# flyBuck_test.net
KiCad netlist of a schematic drawn in EasyEDA Pro
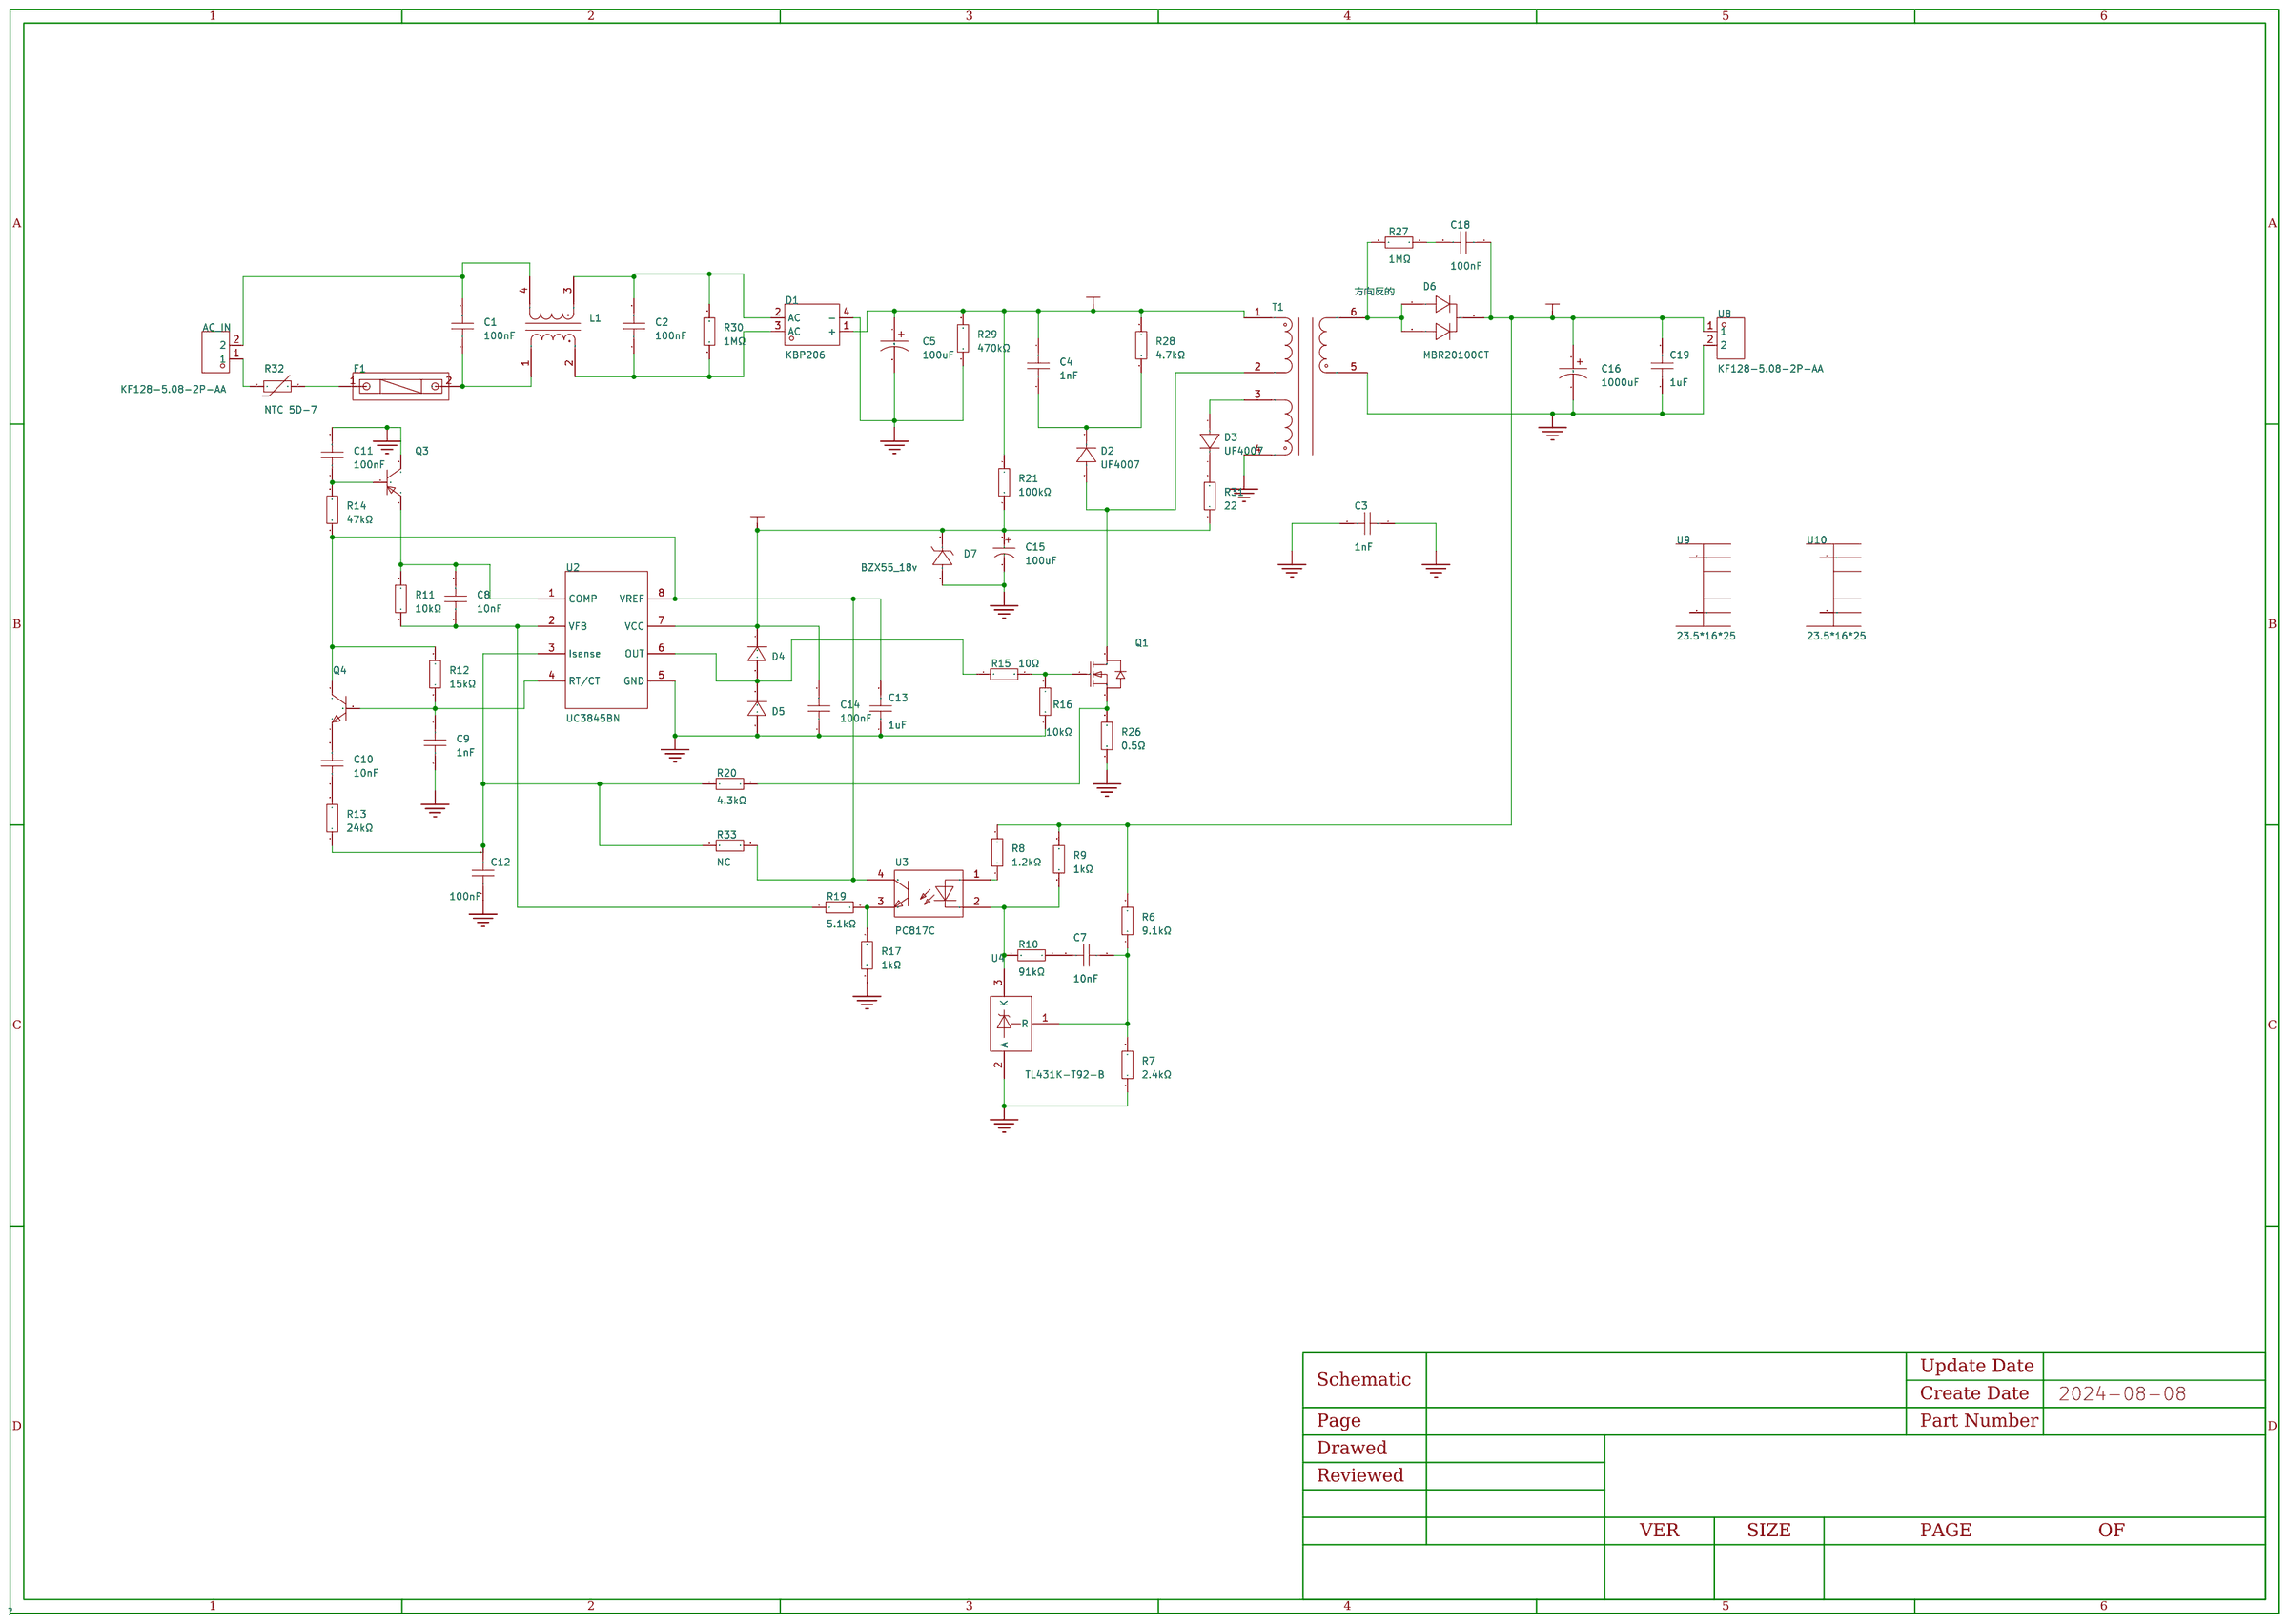
[diagram p0: schematic sheet]

(export (version "E")
  (design (tool "Eeschema 10.0.6"))
  (components
    (comp (ref "AC_IN")
      (value "KF128-5.08-2P-AA")
      (footprint "easyedapro:CONN-TH_P5.08_KF128-5.08-2P")
      (fields (field (name "Manufacturer") "KEFA(科发)"))
      (libsource (lib "easyedapro") (part "KF128-5.08-2P"))
    )
    (comp (ref "C1")
      (value "100nF")
      (footprint "easyedapro:CAP-TH_L13.0-W6.0-P10.0-D0.6")
      (description "容值:100nF;精度:±10%;电压(AC):275V;等级:X2;")
      (fields (field (name "Manufacturer Part") "X2-104K-275VAC") (field (name "Manufacturer") "NDF(达孚)"))
      (libsource (lib "easyedapro") (part "X2-104K-275VAC_C914483"))
    )
    (comp (ref "C2")
      (value "100nF")
      (footprint "easyedapro:CAP-TH_L13.0-W6.0-P10.0-D0.6")
      (description "容值:100nF;精度:±10%;电压(AC):275V;等级:X2;")
      (fields (field (name "Manufacturer Part") "X2-104K-275VAC") (field (name "Manufacturer") "NDF(达孚)"))
      (libsource (lib "easyedapro") (part "X2-104K-275VAC_C914483"))
    )
    (comp (ref "C3")
      (value "1nF")
      (footprint "easyedapro:CAP-TH_L7.0-W3.5-P10.00-D0.6")
      (description "容值:68pF;精度:±10%;电压(AC):400V;等级:Y1;")
      (fields
        (field (name "Manufacturer Part") "Y1680K-E1I-B4-AC400V")
        (field (name "Manufacturer") "Dersonic(德尔创)")
      )
      (libsource (lib "easyedapro") (part "Y1680K-E1I-B4-AC400V"))
    )
    (comp (ref "C4")
      (value "1nF")
      (footprint "easyedapro:CAP-TH_L7.0-W3.5-P10.00-D0.6")
      (description "容值:68pF;精度:±10%;电压(AC):400V;等级:Y1;")
      (fields
        (field (name "Manufacturer Part") "Y1680K-E1I-B4-AC400V")
        (field (name "Manufacturer") "Dersonic(德尔创)")
      )
      (libsource (lib "easyedapro") (part "Y1680K-E1I-B4-AC400V"))
    )
    (comp (ref "C5")
      (value "100uF")
      (footprint "easyedapro:CAP-TH_BD22.0-P10.00-D2.2-FD")
      (description "容值:100uF;精度:±20%;额定电压:400V;脚间距:10mm;纹波电流:630mA@120Hz;")
      (fields (field (name "Manufacturer Part") "152EC0349") (field (name "Manufacturer") "KNSCHA(科尼盛)"))
      (libsource (lib "easyedapro") (part "152EC0349"))
    )
    (comp (ref "C7")
      (value "10nF")
      (footprint "easyedapro:CAP-TH_L5.8-W2.4-P2.54-D0.6")
      (description "容值:100nF;精度:-20%~+80%;额定电压:50V;温度系数:Y5V;")
      (fields
        (field (name "Manufacturer Part") "CC1H104ZA1ED3F5P1100")
        (field (name "Manufacturer") "Dersonic(德尔创)")
      )
      (libsource (lib "easyedapro") (part "CC1H104ZA1ED3F5P1100"))
    )
    (comp (ref "C8")
      (value "10nF")
      (footprint "easyedapro:CAP-TH_L5.8-W2.4-P2.54-D0.6")
      (description "容值:100nF;精度:-20%~+80%;额定电压:50V;温度系数:Y5V;")
      (fields
        (field (name "Manufacturer Part") "CC1H104ZA1ED3F5P1100")
        (field (name "Manufacturer") "Dersonic(德尔创)")
      )
      (libsource (lib "easyedapro") (part "CC1H104ZA1ED3F5P1100"))
    )
    (comp (ref "C9")
      (value "1nF")
      (footprint "easyedapro:CAP-TH_L5.8-W2.4-P2.54-D0.6")
      (description "容值:100nF;精度:-20%~+80%;额定电压:50V;温度系数:Y5V;")
      (fields
        (field (name "Manufacturer Part") "CC1H104ZA1ED3F5P1100")
        (field (name "Manufacturer") "Dersonic(德尔创)")
      )
      (libsource (lib "easyedapro") (part "CC1H104ZA1ED3F5P1100"))
    )
    (comp (ref "C10")
      (value "10nF")
      (footprint "easyedapro:CAP-TH_L5.8-W2.4-P2.54-D0.6")
      (description "容值:100nF;精度:-20%~+80%;额定电压:50V;温度系数:Y5V;")
      (fields
        (field (name "Manufacturer Part") "CC1H104ZA1ED3F5P1100")
        (field (name "Manufacturer") "Dersonic(德尔创)")
      )
      (libsource (lib "easyedapro") (part "CC1H104ZA1ED3F5P1100"))
    )
    (comp (ref "C11")
      (value "100nF")
      (footprint "easyedapro:CAP-TH_L5.8-W2.4-P2.54-D0.6")
      (description "容值:100nF;精度:-20%~+80%;额定电压:50V;温度系数:Y5V;")
      (fields
        (field (name "Manufacturer Part") "CC1H104ZA1ED3F5P1100")
        (field (name "Manufacturer") "Dersonic(德尔创)")
      )
      (libsource (lib "easyedapro") (part "CC1H104ZA1ED3F5P1100"))
    )
    (comp (ref "C12")
      (value "100nF")
      (footprint "easyedapro:CAP-TH_L5.8-W2.4-P2.54-D0.6")
      (description "容值:100nF;精度:-20%~+80%;额定电压:50V;温度系数:Y5V;")
      (fields
        (field (name "Manufacturer Part") "CC1H104ZA1ED3F5P1100")
        (field (name "Manufacturer") "Dersonic(德尔创)")
      )
      (libsource (lib "easyedapro") (part "CC1H104ZA1ED3F5P1100"))
    )
    (comp (ref "C13")
      (value "1uF")
      (footprint "easyedapro:CAP-TH_L6.0-W4.0-P5.00-D1.2")
      (description "等级：独石电容 104K50V  P5 容值：0.1uF 精度：±10% 额定电压：50V 独石电容  积层 X7R MLCC 多层陶瓷")
      (fields (field (name "Manufacturer Part") "CT40805B104K500F3") (field (name "Manufacturer") "KYET(科雅)"))
      (libsource (lib "easyedapro") (part "CT40805B104K500F3"))
    )
    (comp (ref "C14")
      (value "100nF")
      (footprint "easyedapro:CAP-TH_L5.8-W2.4-P2.54-D0.6")
      (description "容值:100nF;精度:-20%~+80%;额定电压:50V;温度系数:Y5V;")
      (fields
        (field (name "Manufacturer Part") "CC1H104ZA1ED3F5P1100")
        (field (name "Manufacturer") "Dersonic(德尔创)")
      )
      (libsource (lib "easyedapro") (part "CC1H104ZA1ED3F5P1100"))
    )
    (comp (ref "C15")
      (value "100uF")
      (footprint "easyedapro:CAP-TH_BD6.3-P2.50-D1.0-FD")
      (description "容值:100uF;精度:±20%;额定电压:25V;")
      (fields (field (name "Manufacturer Part") "ERS1EM101E11OT") (field (name "Manufacturer") "AISHI(艾华集团)"))
      (libsource (lib "easyedapro") (part "ERS1EM101E11OT"))
    )
    (comp (ref "C16")
      (value "1000uF")
      (footprint "easyedapro:CAP-TH_BD10.0-P5.00-D1.0-FD")
      (description "容值:1000uF;精度:±20%;额定电压:25V;纹波电流:450mA@120Hz;等效串联电阻:-;")
      (fields
        (field (name "Manufacturer Part") "01EC4294SHC1000UF25V")
        (field (name "Manufacturer") "KNSCHA(科尼盛)")
      )
      (libsource (lib "easyedapro") (part "01EC4294SHC1000UF25V"))
    )
    (comp (ref "C18")
      (value "100nF")
      (footprint "easyedapro:CAP-TH_L5.8-W2.4-P2.54-D0.6")
      (description "容值:100nF;精度:-20%~+80%;额定电压:50V;温度系数:Y5V;")
      (fields
        (field (name "Manufacturer Part") "CC1H104ZA1ED3F5P1100")
        (field (name "Manufacturer") "Dersonic(德尔创)")
      )
      (libsource (lib "easyedapro") (part "CC1H104ZA1ED3F5P1100"))
    )
    (comp (ref "C19")
      (value "1uF")
      (footprint "easyedapro:CAP-TH_L6.0-W4.0-P5.00-D1.2")
      (description "等级：独石电容 104K50V  P5 容值：0.1uF 精度：±10% 额定电压：50V 独石电容  积层 X7R MLCC 多层陶瓷")
      (fields (field (name "Manufacturer Part") "CT40805B104K500F3") (field (name "Manufacturer") "KYET(科雅)"))
      (libsource (lib "easyedapro") (part "CT40805B104K500F3"))
    )
    (comp (ref "D1")
      (value "KBP206")
      (footprint "easyedapro:KBP_4P-L14.5-W3.5-P3.81-L")
      (description "正向压降(Vf):1.1V@2A;直流反向耐压(Vr):600V;平均整流电流(Io):2A;正向浪涌电流(Ifsm):60A;")
      (fields (field (name "Manufacturer") "HXY MOSFET(华轩阳电子)"))
      (libsource (lib "easyedapro") (part "KBP206_C7507386"))
    )
    (comp (ref "D2")
      (value "UF4007")
      (footprint "easyedapro:DO-41_BD2.4-L4.7-P8.70-D0.9-RD")
      (description "二极管配置:-;正向压降(Vf):1.7V@1A;直流反向耐压(Vr):1kV;整流电流:1A;反向恢复时间(trr):75ns;")
      (fields (field (name "Manufacturer") "MDD(辰达半导体)"))
      (libsource (lib "easyedapro") (part "UF4007_C960666"))
    )
    (comp (ref "D3")
      (value "UF4007")
      (footprint "easyedapro:DO-41_BD2.4-L4.7-P8.70-D0.9-RD")
      (description "二极管配置:-;正向压降(Vf):1.7V@1A;直流反向耐压(Vr):1kV;整流电流:1A;反向恢复时间(trr):75ns;")
      (fields (field (name "Manufacturer") "MDD(辰达半导体)"))
      (libsource (lib "easyedapro") (part "UF4007_C960666"))
    )
    (comp (ref "D4")
      (value "1N4148")
      (footprint "easyedapro:DO-35_BD2.0-L4.2-P8.20-D0.5-RD")
      (description "二极管配置:-;正向压降(Vf):1V@10mA;直流反向耐压(Vr):75V;平均整流电流(Io):150mA;功率:500mW;反向恢复时间(trr):4ns;")
      (fields (field (name "Manufacturer") "LGE(鲁光)"))
      (libsource (lib "easyedapro") (part "1N4148_C402212"))
    )
    (comp (ref "D5")
      (value "1N4148")
      (footprint "easyedapro:DO-35_BD2.0-L4.2-P8.20-D0.5-RD")
      (description "二极管配置:-;正向压降(Vf):1V@10mA;直流反向耐压(Vr):75V;平均整流电流(Io):150mA;功率:500mW;反向恢复时间(trr):4ns;")
      (fields (field (name "Manufacturer") "LGE(鲁光)"))
      (libsource (lib "easyedapro") (part "1N4148_C402212"))
    )
    (comp (ref "D6")
      (value "MBR20100CT")
      (footprint "easyedapro:TO-220AB-3_L10.4-W4.6-P2.54-T")
      (description "二极管配置:1对共阴极;正向压降(Vf):850mV@10A;直流反向耐压(Vr):100V;整流电流:20A;")
      (fields (field (name "Manufacturer") "MDD(辰达半导体)"))
      (libsource (lib "easyedapro") (part "MBR20100CT_C173465"))
    )
    (comp (ref "D7")
      (value "BZX55_18v")
      (footprint "easyedapro:DO-35_BD1.7-L3.6-P10.00-D0.5-FD")
      (description "二极管配置:独立式;稳压值(标称值):9.1V;稳压值(范围):8.65V~9.56V;功率(Pd):500mW;")
      (fields (field (name "Manufacturer") "LGE(鲁光)"))
      (libsource (lib "easyedapro") (part "BZX55C9V1_C5158984"))
    )
    (comp (ref "F1")
      (value "5x20 BLX-A型 保险丝支架 XC-7")
      (footprint "easyedapro:FUSE-TH_L22.6-W9.0")
      (description "保险丝座类型:-;保险丝类型:-;")
      (fields (field (name "Manufacturer") "xcfuse(旭程)"))
      (libsource (lib "easyedapro") (part "5x20 BLX-Atype Fuse holder XC-7"))
    )
    (comp (ref "L1")
      (value "YDUU9.8-103L0301")
      (footprint "easyedapro:FILTER-TH_4P-L16.5-W11.5_YDUU9.8-603L0201")
      (description "线路数:2;电感 @ 频率:10mH@1KHz;")
      (fields (field (name "Manufacturer") "YJYCOIN(益嘉源)"))
      (libsource (lib "easyedapro") (part "YDUU9.8-103L0301"))
    )
    (comp (ref "Q1")
      (value "FQP6N80C")
      (footprint "easyedapro:TO-220-3_L10.2-W4.5-P2.54-L-1")
      (fields (field (name "Manufacturer") "onsemi(安森美)"))
      (libsource (lib "easyedapro") (part "FQP6N80C"))
    )
    (comp (ref "Q3")
      (value "S8550")
      (footprint "easyedapro:TO-92-3_L5.1-W4.1-P1.27-L")
      (description "晶体管类型:PNP;集电极电流(Ic):500mA;集射极击穿电压(Vceo):25V;功率(Pd):625mW;")
      (fields (field (name "Manufacturer") "Slkor(萨科微)"))
      (libsource (lib "easyedapro") (part "S8550_C2826361"))
    )
    (comp (ref "Q4")
      (value "S8050")
      (footprint "easyedapro:TO-92-3_L4.5-W3.5-P1.27-L")
      (description "晶体管类型:NPN;集电极电流(Ic):500mA;集射极击穿电压(Vceo):25V;功率(Pd):625mW;直流电流增益(hFE@Ic,Vce):160@50mA,1V;")
      (fields (field (name "Manufacturer") "JSMSEMI(杰盛微)"))
      (libsource (lib "easyedapro") (part "S8050_C2931492"))
    )
    (comp (ref "R6")
      (value "9.1kΩ")
      (footprint "easyedapro:RES-TH_BD1.9-L3.3-P7.30-D0.5")
      (description "电阻类型:金属膜电阻;阻值:1kΩ;精度:±1%;功率:125mW;温度系数:±50ppm/°C;")
      (fields
        (field (name "Manufacturer Part") "MFR0W8F1001A50")
        (field (name "Manufacturer") "UNI-ROYAL(厚声)")
      )
      (libsource (lib "easyedapro") (part "MFR0W8F1001A50"))
    )
    (comp (ref "R7")
      (value "2.4kΩ")
      (footprint "easyedapro:RES-TH_BD1.9-L3.3-P7.30-D0.5")
      (description "电阻类型:金属膜电阻;阻值:1kΩ;精度:±1%;功率:125mW;温度系数:±50ppm/°C;")
      (fields
        (field (name "Manufacturer Part") "MFR0W8F1001A50")
        (field (name "Manufacturer") "UNI-ROYAL(厚声)")
      )
      (libsource (lib "easyedapro") (part "MFR0W8F1001A50"))
    )
    (comp (ref "R8")
      (value "1.2kΩ")
      (footprint "easyedapro:RES-TH_BD1.9-L3.3-P7.30-D0.5")
      (description "电阻类型:金属膜电阻;阻值:1kΩ;精度:±1%;功率:125mW;温度系数:±50ppm/°C;")
      (fields
        (field (name "Manufacturer Part") "MFR0W8F1001A50")
        (field (name "Manufacturer") "UNI-ROYAL(厚声)")
      )
      (libsource (lib "easyedapro") (part "MFR0W8F1001A50"))
    )
    (comp (ref "R9")
      (value "1kΩ")
      (footprint "easyedapro:RES-TH_BD1.9-L3.3-P7.30-D0.5")
      (description "电阻类型:金属膜电阻;阻值:1kΩ;精度:±1%;功率:125mW;温度系数:±50ppm/°C;")
      (fields
        (field (name "Manufacturer Part") "MFR0W8F1001A50")
        (field (name "Manufacturer") "UNI-ROYAL(厚声)")
      )
      (libsource (lib "easyedapro") (part "MFR0W8F1001A50"))
    )
    (comp (ref "R10")
      (value "91kΩ")
      (footprint "easyedapro:RES-TH_BD1.9-L3.3-P7.30-D0.5")
      (description "电阻类型:金属膜电阻;阻值:1kΩ;精度:±1%;功率:125mW;温度系数:±50ppm/°C;")
      (fields
        (field (name "Manufacturer Part") "MFR0W8F1001A50")
        (field (name "Manufacturer") "UNI-ROYAL(厚声)")
      )
      (libsource (lib "easyedapro") (part "MFR0W8F1001A50"))
    )
    (comp (ref "R11")
      (value "10kΩ")
      (footprint "easyedapro:RES-TH_BD1.9-L3.3-P7.30-D0.5")
      (description "电阻类型:金属膜电阻;阻值:1kΩ;精度:±1%;功率:125mW;温度系数:±50ppm/°C;")
      (fields
        (field (name "Manufacturer Part") "MFR0W8F1001A50")
        (field (name "Manufacturer") "UNI-ROYAL(厚声)")
      )
      (libsource (lib "easyedapro") (part "MFR0W8F1001A50"))
    )
    (comp (ref "R12")
      (value "15kΩ")
      (footprint "easyedapro:RES-TH_BD1.9-L3.3-P7.30-D0.5")
      (description "电阻类型:金属膜电阻;阻值:1kΩ;精度:±1%;功率:125mW;温度系数:±50ppm/°C;")
      (fields
        (field (name "Manufacturer Part") "MFR0W8F1001A50")
        (field (name "Manufacturer") "UNI-ROYAL(厚声)")
      )
      (libsource (lib "easyedapro") (part "MFR0W8F1001A50"))
    )
    (comp (ref "R13")
      (value "24kΩ")
      (footprint "easyedapro:RES-TH_BD1.9-L3.3-P7.30-D0.5")
      (description "电阻类型:金属膜电阻;阻值:1kΩ;精度:±1%;功率:125mW;温度系数:±50ppm/°C;")
      (fields
        (field (name "Manufacturer Part") "MFR0W8F1001A50")
        (field (name "Manufacturer") "UNI-ROYAL(厚声)")
      )
      (libsource (lib "easyedapro") (part "MFR0W8F1001A50"))
    )
    (comp (ref "R14")
      (value "47kΩ")
      (footprint "easyedapro:RES-TH_BD1.9-L3.3-P7.30-D0.5")
      (description "电阻类型:金属膜电阻;阻值:1kΩ;精度:±1%;功率:125mW;温度系数:±50ppm/°C;")
      (fields
        (field (name "Manufacturer Part") "MFR0W8F1001A50")
        (field (name "Manufacturer") "UNI-ROYAL(厚声)")
      )
      (libsource (lib "easyedapro") (part "MFR0W8F1001A50"))
    )
    (comp (ref "R15")
      (value "10Ω")
      (footprint "easyedapro:RES-TH_BD1.9-L3.3-P7.30-D0.5")
      (description "电阻类型:金属膜电阻;阻值:1kΩ;精度:±1%;功率:125mW;温度系数:±50ppm/°C;")
      (fields
        (field (name "Manufacturer Part") "MFR0W8F1001A50")
        (field (name "Manufacturer") "UNI-ROYAL(厚声)")
      )
      (libsource (lib "easyedapro") (part "MFR0W8F1001A50"))
    )
    (comp (ref "R16")
      (value "10kΩ")
      (footprint "easyedapro:RES-TH_BD1.9-L3.3-P7.30-D0.5")
      (description "电阻类型:金属膜电阻;阻值:1kΩ;精度:±1%;功率:125mW;温度系数:±50ppm/°C;")
      (fields
        (field (name "Manufacturer Part") "MFR0W8F1001A50")
        (field (name "Manufacturer") "UNI-ROYAL(厚声)")
      )
      (libsource (lib "easyedapro") (part "MFR0W8F1001A50"))
    )
    (comp (ref "R17")
      (value "1kΩ")
      (footprint "easyedapro:RES-TH_BD1.9-L3.3-P7.30-D0.5")
      (description "电阻类型:金属膜电阻;阻值:1kΩ;精度:±1%;功率:125mW;温度系数:±50ppm/°C;")
      (fields
        (field (name "Manufacturer Part") "MFR0W8F1001A50")
        (field (name "Manufacturer") "UNI-ROYAL(厚声)")
      )
      (libsource (lib "easyedapro") (part "MFR0W8F1001A50"))
    )
    (comp (ref "R19")
      (value "5.1kΩ")
      (footprint "easyedapro:RES-TH_BD1.9-L3.3-P7.30-D0.5")
      (description "电阻类型:金属膜电阻;阻值:1kΩ;精度:±1%;功率:125mW;温度系数:±50ppm/°C;")
      (fields
        (field (name "Manufacturer Part") "MFR0W8F1001A50")
        (field (name "Manufacturer") "UNI-ROYAL(厚声)")
      )
      (libsource (lib "easyedapro") (part "MFR0W8F1001A50"))
    )
    (comp (ref "R20")
      (value "4.3kΩ")
      (footprint "easyedapro:RES-TH_BD1.9-L3.3-P7.30-D0.5")
      (description "电阻类型:金属膜电阻;阻值:1kΩ;精度:±1%;功率:125mW;温度系数:±50ppm/°C;")
      (fields
        (field (name "Manufacturer Part") "MFR0W8F1001A50")
        (field (name "Manufacturer") "UNI-ROYAL(厚声)")
      )
      (libsource (lib "easyedapro") (part "MFR0W8F1001A50"))
    )
    (comp (ref "R21")
      (value "100kΩ")
      (footprint "easyedapro:RES-TH_BD2.2-L6.5-P10.50-D0.6")
      (description "电阻类型:金属膜电阻;阻值:4.7kΩ;精度:±1%;功率:250mW;温度系数:±50ppm/°C;")
      (fields (field (name "Manufacturer Part") "MF1/4CCT52A4701F") (field (name "Manufacturer") "KOA"))
      (libsource (lib "easyedapro") (part "MF1/4CCT52A4701F"))
    )
    (comp (ref "R26")
      (value "0.5Ω")
      (footprint "easyedapro:R1206")
      (libsource (lib "easyedapro") (part "电阻"))
    )
    (comp (ref "R27")
      (value "1MΩ")
      (footprint "easyedapro:RES-TH_BD2.2-L6.5-P10.50-D0.6")
      (description "电阻类型:金属膜电阻;阻值:4.7kΩ;精度:±1%;功率:250mW;温度系数:±50ppm/°C;")
      (fields (field (name "Manufacturer Part") "MF1/4CCT52A4701F") (field (name "Manufacturer") "KOA"))
      (libsource (lib "easyedapro") (part "MF1/4CCT52A4701F"))
    )
    (comp (ref "R28")
      (value "4.7kΩ")
      (footprint "easyedapro:RES-TH_BD2.2-L6.5-P10.50-D0.6")
      (description "电阻类型:金属膜电阻;阻值:4.7kΩ;精度:±1%;功率:250mW;温度系数:±50ppm/°C;")
      (fields (field (name "Manufacturer Part") "MF1/4CCT52A4701F") (field (name "Manufacturer") "KOA"))
      (libsource (lib "easyedapro") (part "MF1/4CCT52A4701F"))
    )
    (comp (ref "R29")
      (value "470kΩ")
      (footprint "easyedapro:RES-TH_BD2.2-L6.5-P10.50-D0.6")
      (description "电阻类型:金属膜电阻;阻值:4.7kΩ;精度:±1%;功率:250mW;温度系数:±50ppm/°C;")
      (fields (field (name "Manufacturer Part") "MF1/4CCT52A4701F") (field (name "Manufacturer") "KOA"))
      (libsource (lib "easyedapro") (part "MF1/4CCT52A4701F"))
    )
    (comp (ref "R30")
      (value "1MΩ")
      (footprint "easyedapro:RES-TH_BD2.3-L6.5-P10.50-D0.5")
      (description "电阻类型:玻璃釉电阻;阻值:10kΩ;精度:±5%;功率:250mW;温度系数:±200ppm/°C;")
      (fields (field (name "Manufacturer Part") "RI40-1/4W-10KΩ±5%T") (field (name "Manufacturer") "华星机电"))
      (libsource (lib "easyedapro") (part "RI40-1/4W-10KΩ±5%T"))
    )
    (comp (ref "R31") (value "22") (footprint "easyedapro:R1206") (libsource (lib "easyedapro") (part "电阻")))
    (comp (ref "R32")
      (value "NTC 5D-7")
      (footprint "easyedapro:RES-TH_L8.5-W5.5-P5.00-D0.6-S5.50")
      (description "阻值(25°C):5Ω;B值(25°C/50°C):-;电阻精度:-;功率:-;B值精度:-;最大稳态电流(25°C):2A;")
      (fields (field (name "Manufacturer") "RUILON(瑞隆源)"))
      (libsource (lib "easyedapro") (part "NTC 5D-7"))
    )
    (comp (ref "R33")
      (value "NC")
      (footprint "easyedapro:RES-TH_BD1.9-L3.3-P7.30-D0.5")
      (description "电阻类型:金属膜电阻;阻值:1kΩ;精度:±1%;功率:125mW;温度系数:±50ppm/°C;")
      (fields
        (field (name "Manufacturer Part") "MFR0W8F1001A50")
        (field (name "Manufacturer") "UNI-ROYAL(厚声)")
      )
      (libsource (lib "easyedapro") (part "MFR0W8F1001A50"))
    )
    (comp (ref "T1")
      (value "~")
      (footprint "easyedapro:EE25_7P")
      (libsource (lib "easyedapro") (part "EE25_7P"))
    )
    (comp (ref "U2")
      (value "UC3845BN")
      (footprint "easyedapro:DIP-8_L10.9-W6.6-P2.54-LS7.6-BL")
      (description "电源电压:7.6V~30V;开关频率:500kHz;")
      (fields (field (name "Manufacturer") "ST(意法半导体)"))
      (libsource (lib "easyedapro") (part "UC3845B"))
    )
    (comp (ref "U3")
      (value "PC817C")
      (footprint "easyedapro:DIP-4_L4.6-W6.5-P2.54-LS7.6-BL")
      (fields (field (name "Manufacturer") "GOODWORK(固得沃克)"))
      (libsource (lib "easyedapro") (part "PC817C_C3025068"))
    )
    (comp (ref "U4")
      (value "TL431K-T92-B")
      (footprint "easyedapro:TO-92-3_L4.9-W3.7-P1.27-L")
      (description "输出类型:可编程;输入电压:2.495V;输出电压:2.5V~36V;输出电流:100mA;")
      (fields (field (name "Manufacturer") "UTC(友顺)"))
      (libsource (lib "easyedapro") (part "TL431K-T92-B"))
    )
    (comp (ref "U8")
      (value "KF128-5.08-2P-AA")
      (footprint "easyedapro:CONN-TH_P5.08_KF128-5.08-2P")
      (fields (field (name "Manufacturer") "KEFA(科发)"))
      (libsource (lib "easyedapro") (part "KF128-5.08-2P"))
    )
    (comp (ref "U9")
      (value "23.5*16*25")
      (footprint "easyedapro:HEATSINK-TH_L23.5-W16.0-P18.0_XSD2156-067")
      (description "产品尺寸:23.5*16*25MM;材 质:6063-T5铝;")
      (fields (field (name "Manufacturer") "XSD(鑫顺达)"))
      (libsource (lib "easyedapro") (part "23.5*16*25 2个钉散热片"))
    )
    (comp (ref "U10")
      (value "23.5*16*25")
      (footprint "easyedapro:HEATSINK-TH_L23.5-W16.0-P18.0_XSD2156-067")
      (description "产品尺寸:23.5*16*25MM;材 质:6063-T5铝;")
      (fields (field (name "Manufacturer") "XSD(鑫顺达)"))
      (libsource (lib "easyedapro") (part "23.5*16*25 2个钉散热片"))
    )
  )
  (nets
    (net (code "1") (name "+15V") (class "Default")
      (node (ref "C16") (pin "1") (pinfunction "1_1") (pintype "unspecified"))
      (node (ref "C18") (pin "1") (pinfunction "1_1") (pintype "unspecified"))
      (node (ref "C19") (pin "2") (pinfunction "2_2") (pintype "unspecified"))
      (node (ref "D6") (pin "2") (pinfunction "C_2") (pintype "unspecified"))
      (node (ref "R6") (pin "2") (pinfunction "2_2") (pintype "input"))
      (node (ref "R8") (pin "2") (pinfunction "2_2") (pintype "input"))
      (node (ref "R9") (pin "2") (pinfunction "2_2") (pintype "input"))
      (node (ref "U8") (pin "1") (pinfunction "1_1") (pintype "unspecified"))
    )
    (net (code "2") (name "GND") (class "Default")
      (node (ref "C16") (pin "2") (pinfunction "2_2") (pintype "unspecified"))
      (node (ref "C19") (pin "1") (pinfunction "1_1") (pintype "unspecified"))
      (node (ref "C3") (pin "1") (pinfunction "1_1") (pintype "unspecified"))
      (node (ref "R7") (pin "1") (pinfunction "1_1") (pintype "input"))
      (node (ref "T1") (pin "5") (pinfunction "5_5") (pintype "unspecified"))
      (node (ref "U4") (pin "2") (pinfunction "A_2") (pintype "unspecified"))
      (node (ref "U8") (pin "2") (pinfunction "2_2") (pintype "unspecified"))
    )
    (net (code "3") (name "Net-(AC_IN-Pad1)") (class "Default")
      (node (ref "AC_IN") (pin "1") (pinfunction "1_1") (pintype "unspecified"))
      (node (ref "R32") (pin "1") (pinfunction "1_1") (pintype "input"))
    )
    (net (code "4") (name "Net-(AC_IN-Pad2)") (class "Default")
      (node (ref "AC_IN") (pin "2") (pinfunction "2_2") (pintype "unspecified"))
      (node (ref "C1") (pin "2") (pinfunction "2_2") (pintype "unspecified"))
      (node (ref "L1") (pin "4") (pinfunction "4_4") (pintype "unspecified"))
    )
    (net (code "5") (name "Net-(C1-Pad1)") (class "Default")
      (node (ref "C1") (pin "1") (pinfunction "1_1") (pintype "unspecified"))
      (node (ref "F1") (pin "2") (pinfunction "2_2") (pintype "unspecified"))
      (node (ref "L1") (pin "1") (pinfunction "1_1") (pintype "unspecified"))
    )
    (net (code "6") (name "Net-(C2-Pad1)") (class "Default")
      (node (ref "C2") (pin "1") (pinfunction "1_1") (pintype "unspecified"))
      (node (ref "D1") (pin "3") (pinfunction "AC_3") (pintype "unspecified"))
      (node (ref "L1") (pin "2") (pinfunction "2_2") (pintype "unspecified"))
      (node (ref "R30") (pin "1") (pinfunction "1_1") (pintype "unspecified"))
    )
    (net (code "7") (name "Net-(C2-Pad2)") (class "Default")
      (node (ref "C2") (pin "2") (pinfunction "2_2") (pintype "unspecified"))
      (node (ref "D1") (pin "2") (pinfunction "AC_2") (pintype "unspecified"))
      (node (ref "L1") (pin "3") (pinfunction "3_3") (pintype "unspecified"))
      (node (ref "R30") (pin "2") (pinfunction "2_2") (pintype "unspecified"))
    )
    (net (code "8") (name "Net-(C7-Pad1)") (class "Default")
      (node (ref "C7") (pin "1") (pinfunction "1_1") (pintype "unspecified"))
      (node (ref "R10") (pin "1") (pinfunction "1_1") (pintype "input"))
    )
    (net (code "9") (name "Net-(C10-Pad1)") (class "Default")
      (node (ref "C10") (pin "1") (pinfunction "1_1") (pintype "unspecified"))
      (node (ref "R13") (pin "2") (pinfunction "2_2") (pintype "input"))
    )
    (net (code "10") (name "Net-(C18-Pad2)") (class "Default")
      (node (ref "C18") (pin "2") (pinfunction "2_2") (pintype "unspecified"))
      (node (ref "R27") (pin "1") (pinfunction "1_1") (pintype "unspecified"))
    )
    (net (code "11") (name "Net-(D2-A)") (class "Default")
      (node (ref "D2") (pin "2") (pinfunction "A_2") (pintype "unspecified"))
      (node (ref "Q1") (pin "2") (pinfunction "D_2") (pintype "unspecified"))
      (node (ref "T1") (pin "2") (pinfunction "2_2") (pintype "unspecified"))
    )
    (net (code "12") (name "Net-(D2-K)") (class "Default")
      (node (ref "C4") (pin "2") (pinfunction "2_2") (pintype "unspecified"))
      (node (ref "D2") (pin "1") (pinfunction "K_1") (pintype "unspecified"))
      (node (ref "R28") (pin "1") (pinfunction "1_1") (pintype "unspecified"))
    )
    (net (code "13") (name "Net-(D3-A)") (class "Default")
      (node (ref "D3") (pin "2") (pinfunction "A_2") (pintype "unspecified"))
      (node (ref "T1") (pin "3") (pinfunction "3_3") (pintype "unspecified"))
    )
    (net (code "14") (name "Net-(D3-K)") (class "Default")
      (node (ref "D3") (pin "1") (pinfunction "K_1") (pintype "unspecified"))
      (node (ref "R31") (pin "2") (pinfunction "2_2") (pintype "input"))
    )
    (net (code "15") (name "Net-(D4-A)") (class "Default")
      (node (ref "D4") (pin "2") (pinfunction "A_2") (pintype "unspecified"))
      (node (ref "D5") (pin "1") (pinfunction "C_1") (pintype "unspecified"))
      (node (ref "R15") (pin "2") (pinfunction "2_2") (pintype "input"))
      (node (ref "U2") (pin "6") (pinfunction "OUT_6") (pintype "unspecified"))
    )
    (net (code "16") (name "Net-(D6-A-Pad1)") (class "Default")
      (node (ref "D6") (pin "1") (pinfunction "A_1") (pintype "unspecified"))
      (node (ref "D6") (pin "3") (pinfunction "A_3") (pintype "unspecified"))
      (node (ref "R27") (pin "2") (pinfunction "2_2") (pintype "unspecified"))
      (node (ref "T1") (pin "6") (pinfunction "6_6") (pintype "unspecified"))
    )
    (net (code "17") (name "Net-(F1-Pad1)") (class "Default")
      (node (ref "F1") (pin "1") (pinfunction "1_1") (pintype "unspecified"))
      (node (ref "R32") (pin "2") (pinfunction "2_2") (pintype "input"))
    )
    (net (code "18") (name "Net-(Q1-G)") (class "Default")
      (node (ref "Q1") (pin "1") (pinfunction "G_1") (pintype "unspecified"))
      (node (ref "R15") (pin "1") (pinfunction "1_1") (pintype "input"))
      (node (ref "R16") (pin "1") (pinfunction "1_1") (pintype "input"))
    )
    (net (code "19") (name "Net-(Q1-S)") (class "Default")
      (node (ref "Q1") (pin "3") (pinfunction "S_3") (pintype "unspecified"))
      (node (ref "R20") (pin "2") (pinfunction "2_2") (pintype "input"))
      (node (ref "R26") (pin "2") (pinfunction "2_2") (pintype "input"))
    )
    (net (code "20") (name "Net-(Q3-B)") (class "Default")
      (node (ref "C11") (pin "1") (pinfunction "1_1") (pintype "unspecified"))
      (node (ref "Q3") (pin "2") (pinfunction "B_2") (pintype "unspecified"))
      (node (ref "R14") (pin "2") (pinfunction "2_2") (pintype "input"))
    )
    (net (code "21") (name "Net-(Q3-E)") (class "Default")
      (node (ref "C8") (pin "2") (pinfunction "2_2") (pintype "unspecified"))
      (node (ref "Q3") (pin "1") (pinfunction "E_1") (pintype "unspecified"))
      (node (ref "R11") (pin "2") (pinfunction "2_2") (pintype "input"))
      (node (ref "U2") (pin "1") (pinfunction "COMP_1") (pintype "unspecified"))
    )
    (net (code "22") (name "Net-(Q4-B)") (class "Default")
      (node (ref "C9") (pin "2") (pinfunction "2_2") (pintype "unspecified"))
      (node (ref "Q4") (pin "2") (pinfunction "B_2") (pintype "unspecified"))
      (node (ref "R12") (pin "1") (pinfunction "1_1") (pintype "input"))
      (node (ref "U2") (pin "4") (pinfunction "RT/CT_4") (pintype "unspecified"))
    )
    (net (code "23") (name "Net-(Q4-C)") (class "Default")
      (node (ref "C13") (pin "2") (pinfunction "2_2") (pintype "unspecified"))
      (node (ref "Q4") (pin "3") (pinfunction "C_3") (pintype "unspecified"))
      (node (ref "R12") (pin "2") (pinfunction "2_2") (pintype "input"))
      (node (ref "R14") (pin "1") (pinfunction "1_1") (pintype "input"))
      (node (ref "R33") (pin "2") (pinfunction "2_2") (pintype "input"))
      (node (ref "U2") (pin "8") (pinfunction "VREF_8") (pintype "unspecified"))
      (node (ref "U3") (pin "4") (pinfunction "COL_4") (pintype "unspecified"))
    )
    (net (code "24") (name "Net-(Q4-E)") (class "Default")
      (node (ref "C10") (pin "2") (pinfunction "2_2") (pintype "unspecified"))
      (node (ref "Q4") (pin "1") (pinfunction "E_1") (pintype "unspecified"))
    )
    (net (code "25") (name "Net-(U2-Isense)") (class "Default")
      (node (ref "C12") (pin "2") (pinfunction "2_2") (pintype "unspecified"))
      (node (ref "R13") (pin "1") (pinfunction "1_1") (pintype "input"))
      (node (ref "R20") (pin "1") (pinfunction "1_1") (pintype "input"))
      (node (ref "R33") (pin "1") (pinfunction "1_1") (pintype "input"))
      (node (ref "U2") (pin "3") (pinfunction "Isense_3") (pintype "unspecified"))
    )
    (net (code "26") (name "Net-(U2-VFB)") (class "Default")
      (node (ref "C8") (pin "1") (pinfunction "1_1") (pintype "unspecified"))
      (node (ref "R11") (pin "1") (pinfunction "1_1") (pintype "input"))
      (node (ref "R19") (pin "1") (pinfunction "1_1") (pintype "input"))
      (node (ref "U2") (pin "2") (pinfunction "VFB_2") (pintype "unspecified"))
    )
    (net (code "27") (name "Net-(U3-AN)") (class "Default")
      (node (ref "R8") (pin "1") (pinfunction "1_1") (pintype "input"))
      (node (ref "U3") (pin "1") (pinfunction "AN_1") (pintype "unspecified"))
    )
    (net (code "28") (name "Net-(U3-CAT)") (class "Default")
      (node (ref "R10") (pin "2") (pinfunction "2_2") (pintype "input"))
      (node (ref "R9") (pin "1") (pinfunction "1_1") (pintype "input"))
      (node (ref "U3") (pin "2") (pinfunction "CAT_2") (pintype "unspecified"))
      (node (ref "U4") (pin "3") (pinfunction "K_3") (pintype "unspecified"))
    )
    (net (code "29") (name "Net-(U3-EM)") (class "Default")
      (node (ref "R17") (pin "1") (pinfunction "1_1") (pintype "input"))
      (node (ref "R19") (pin "2") (pinfunction "2_2") (pintype "input"))
      (node (ref "U3") (pin "3") (pinfunction "EM_3") (pintype "unspecified"))
    )
    (net (code "30") (name "Net-(U4-R)") (class "Default")
      (node (ref "C7") (pin "2") (pinfunction "2_2") (pintype "unspecified"))
      (node (ref "R6") (pin "1") (pinfunction "1_1") (pintype "input"))
      (node (ref "R7") (pin "2") (pinfunction "2_2") (pintype "input"))
      (node (ref "U4") (pin "1") (pinfunction "R_1") (pintype "unspecified"))
    )
    (net (code "31") (name "PGND") (class "Default")
      (node (ref "C11") (pin "2") (pinfunction "2_2") (pintype "unspecified"))
      (node (ref "C12") (pin "1") (pinfunction "1_1") (pintype "unspecified"))
      (node (ref "C13") (pin "1") (pinfunction "1_1") (pintype "unspecified"))
      (node (ref "C14") (pin "1") (pinfunction "1_1") (pintype "unspecified"))
      (node (ref "C15") (pin "2") (pinfunction "2_2") (pintype "input"))
      (node (ref "C3") (pin "2") (pinfunction "2_2") (pintype "unspecified"))
      (node (ref "C5") (pin "2") (pinfunction "2_2") (pintype "unspecified"))
      (node (ref "C9") (pin "1") (pinfunction "1_1") (pintype "unspecified"))
      (node (ref "D1") (pin "4") (pinfunction "-_4") (pintype "unspecified"))
      (node (ref "D5") (pin "2") (pinfunction "A_2") (pintype "unspecified"))
      (node (ref "D7") (pin "1") (pinfunction "K_1") (pintype "unspecified"))
      (node (ref "Q3") (pin "3") (pinfunction "C_3") (pintype "unspecified"))
      (node (ref "R16") (pin "2") (pinfunction "2_2") (pintype "input"))
      (node (ref "R17") (pin "2") (pinfunction "2_2") (pintype "input"))
      (node (ref "R26") (pin "1") (pinfunction "1_1") (pintype "input"))
      (node (ref "R29") (pin "1") (pinfunction "1_1") (pintype "unspecified"))
      (node (ref "T1") (pin "4") (pinfunction "4_4") (pintype "unspecified"))
      (node (ref "U2") (pin "5") (pinfunction "GND_5") (pintype "unspecified"))
    )
    (net (code "32") (name "UC_VCC") (class "Default")
      (node (ref "C14") (pin "2") (pinfunction "2_2") (pintype "unspecified"))
      (node (ref "C15") (pin "1") (pinfunction "1_1") (pintype "input"))
      (node (ref "D4") (pin "1") (pinfunction "C_1") (pintype "unspecified"))
      (node (ref "D7") (pin "2") (pinfunction "A_2") (pintype "unspecified"))
      (node (ref "R21") (pin "2") (pinfunction "2_2") (pintype "unspecified"))
      (node (ref "R31") (pin "1") (pinfunction "1_1") (pintype "input"))
      (node (ref "U2") (pin "7") (pinfunction "VCC_7") (pintype "unspecified"))
    )
    (net (code "33") (name "VBUS") (class "Default")
      (node (ref "C4") (pin "1") (pinfunction "1_1") (pintype "unspecified"))
      (node (ref "C5") (pin "1") (pinfunction "1_1") (pintype "unspecified"))
      (node (ref "D1") (pin "1") (pinfunction "+_1") (pintype "unspecified"))
      (node (ref "R21") (pin "1") (pinfunction "1_1") (pintype "unspecified"))
      (node (ref "R28") (pin "2") (pinfunction "2_2") (pintype "unspecified"))
      (node (ref "R29") (pin "2") (pinfunction "2_2") (pintype "unspecified"))
      (node (ref "T1") (pin "1") (pinfunction "1_1") (pintype "unspecified"))
    )
    (net (code "34") (name "unconnected-(U9-Pad1)") (class "Default")
      (node (ref "U9") (pin "1") (pinfunction "1_1") (pintype "unspecified"))
    )
    (net (code "35") (name "unconnected-(U9-Pad2)") (class "Default")
      (node (ref "U9") (pin "2") (pinfunction "2_2") (pintype "unspecified"))
    )
    (net (code "36") (name "unconnected-(U10-Pad1)") (class "Default")
      (node (ref "U10") (pin "1") (pinfunction "1_1") (pintype "unspecified"))
    )
    (net (code "37") (name "unconnected-(U10-Pad2)") (class "Default")
      (node (ref "U10") (pin "2") (pinfunction "2_2") (pintype "unspecified"))
    )
  )
)
